# ethernet.net
KiCad netlist of a schematic drawn in Altium Designer
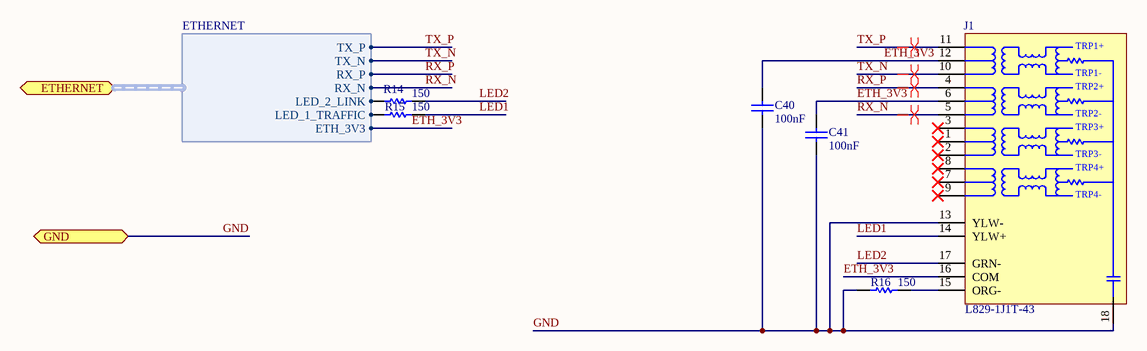
[diagram p0: ethernet.SchDoc]

(export (version "E")
  (design (tool "Eeschema 10.0.6"))
  (components
    (comp (ref "C40")
      (value "100nF")
      (footprint "0805")
      (fields (field (name "TOLERANCE") "5%") (field (name "VOLTAGE") "10V") (field (name "Comment") "CAP"))
      (libsource (lib "gasctrl") (part "CAP"))
    )
    (comp (ref "C41")
      (value "100nF")
      (footprint "0805")
      (fields (field (name "TOLERANCE") "5%") (field (name "VOLTAGE") "10V") (field (name "Comment") "CAP"))
      (libsource (lib "gasctrl") (part "CAP"))
    )
    (comp (ref "J1")
      (value "L829-1J1T-43")
      (footprint "gasctrl:L829-1J1T-43")
      (description "MagJack 12-core 10/100/1000 Base-T Ethernet Connector")
      (fields (field (name "MANUFACTURER") "Bell Fuse Inc."))
      (libsource (lib "openrd") (part "L829-1J1T-43"))
    )
    (comp (ref "R14")
      (value "150")
      (footprint "0805")
      (fields (field (name "TOLERANCE") "5%") (field (name "Comment") "RES"))
      (libsource (lib "gasctrl") (part "RES"))
    )
    (comp (ref "R15")
      (value "150")
      (footprint "0805")
      (fields (field (name "TOLERANCE") "5%") (field (name "Comment") "RES"))
      (libsource (lib "gasctrl") (part "RES"))
    )
    (comp (ref "R16")
      (value "150")
      (footprint "0805")
      (fields (field (name "TOLERANCE") "5%") (field (name "Comment") "RES"))
      (libsource (lib "gasctrl") (part "RES"))
    )
  )
  (nets
    (net (code "2") (name "/ETH_3V3") (class "Default")
      (node (ref "C40") (pin "2") (pinfunction "2_2") (pintype "passive"))
      (node (ref "C41") (pin "2") (pinfunction "2_2") (pintype "passive"))
      (node (ref "J1") (pin "12") (pinfunction "TRCT1_12") (pintype "passive"))
      (node (ref "J1") (pin "16") (pinfunction "COM_16") (pintype "passive"))
      (node (ref "J1") (pin "6") (pinfunction "TRCT2_6") (pintype "passive"))
    )
    (net (code "3") (name "/GND") (class "Default")
      (node (ref "C40") (pin "1") (pinfunction "1_1") (pintype "passive"))
      (node (ref "C41") (pin "1") (pinfunction "1_1") (pintype "passive"))
      (node (ref "J1") (pin "13") (pinfunction "YLW-_13") (pintype "passive"))
      (node (ref "J1") (pin "18") (pinfunction "SHEILD_18") (pintype "passive"))
      (node (ref "R16") (pin "1") (pinfunction "1_1") (pintype "passive"))
    )
    (net (code "4") (name "/LED1") (class "Default")
      (node (ref "J1") (pin "14") (pinfunction "YLW+_14") (pintype "passive"))
      (node (ref "R15") (pin "2") (pinfunction "2_2") (pintype "passive"))
    )
    (net (code "5") (name "/LED2") (class "Default")
      (node (ref "J1") (pin "17") (pinfunction "GRN-_17") (pintype "passive"))
      (node (ref "R14") (pin "2") (pinfunction "2_2") (pintype "passive"))
    )
    (net (code "6") (name "/LED_1_TRAFFIC") (class "Default")
      (node (ref "R15") (pin "1") (pinfunction "1_1") (pintype "passive"))
    )
    (net (code "7") (name "/LED_2_LINK") (class "Default")
      (node (ref "R14") (pin "1") (pinfunction "1_1") (pintype "passive"))
    )
    (net (code "8") (name "/RX_N") (class "Default")
      (node (ref "J1") (pin "5") (pinfunction "TRD2-_5") (pintype "passive"))
    )
    (net (code "9") (name "/RX_P") (class "Default")
      (node (ref "J1") (pin "4") (pinfunction "TRD2+_4") (pintype "passive"))
    )
    (net (code "10") (name "/TX_N") (class "Default")
      (node (ref "J1") (pin "10") (pinfunction "TRD1-_10") (pintype "passive"))
    )
    (net (code "11") (name "/TX_P") (class "Default")
      (node (ref "J1") (pin "11") (pinfunction "TRD1+_11") (pintype "passive"))
    )
    (net (code "13") (name "Net-(J1-ORG-)") (class "Default")
      (node (ref "J1") (pin "15") (pinfunction "ORG-_15") (pintype "passive"))
      (node (ref "R16") (pin "2") (pinfunction "2_2") (pintype "passive"))
    )
    (net (code "14") (name "unconnected-(J1-TRCT3-Pad1)") (class "Default")
      (node (ref "J1") (pin "1") (pinfunction "TRCT3_1") (pintype "passive+no_connect"))
    )
    (net (code "15") (name "unconnected-(J1-TRCT4-Pad7)") (class "Default")
      (node (ref "J1") (pin "7") (pinfunction "TRCT4_7") (pintype "passive+no_connect"))
    )
    (net (code "16") (name "unconnected-(J1-TRD3+-Pad3)") (class "Default")
      (node (ref "J1") (pin "3") (pinfunction "TRD3+_3") (pintype "passive+no_connect"))
    )
    (net (code "17") (name "unconnected-(J1-TRD3--Pad2)") (class "Default")
      (node (ref "J1") (pin "2") (pinfunction "TRD3-_2") (pintype "passive+no_connect"))
    )
    (net (code "18") (name "unconnected-(J1-TRD4+-Pad8)") (class "Default")
      (node (ref "J1") (pin "8") (pinfunction "TRD4+_8") (pintype "passive+no_connect"))
    )
    (net (code "19") (name "unconnected-(J1-TRD4--Pad9)") (class "Default")
      (node (ref "J1") (pin "9") (pinfunction "TRD4-_9") (pintype "passive+no_connect"))
    )
  )
)
